# 02_-_MCU.net
KiCad netlist of a schematic drawn in Altium Designer
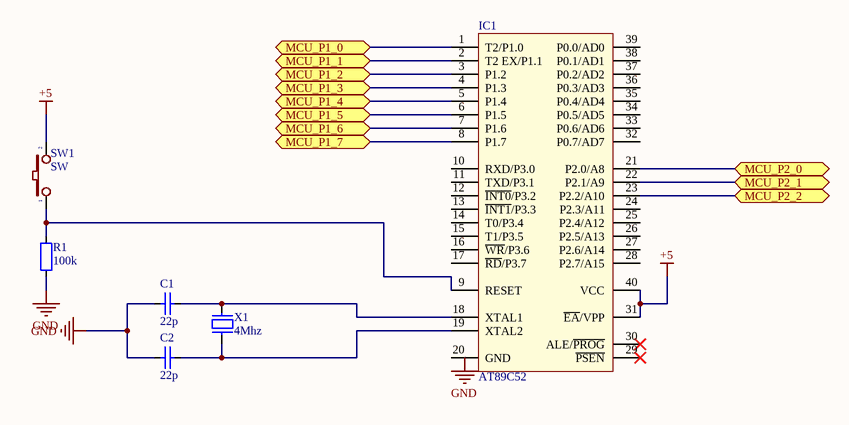
[diagram p0: 02 - MCU.SchDoc]

(export (version "E")
  (design (tool "Eeschema 10.0.6"))
  (components
    (comp (ref "C1")
      (value "22p")
      (footprint "CAP_0402")
      (description "Capacitor")
      (fields (field (name "PUBLISHER") "Altium Limited"))
      (libsource (lib "My Library.~(5)") (part "CapSMD"))
    )
    (comp (ref "C2")
      (value "22p")
      (footprint "CAP_0402")
      (description "Capacitor")
      (fields (field (name "PUBLISHER") "Altium Limited"))
      (libsource (lib "My Library.~(5)") (part "CapSMD"))
    )
    (comp (ref "IC1")
      (value "AT89C52")
      (footprint "DIP40/W0.6")
      (description "Atmel AT89C52, 8k Byte Flash Memory , 40 Pin")
      (libsource (lib "My Library.~(1)") (part "AT89C52"))
    )
    (comp (ref "R1")
      (value "100k")
      (footprint "RES-SMD-0101")
      (description "Resistor")
      (fields
        (field (name "MANUFACTURER") "Generic Components")
        (field (name "PUBLISHER") "Altium Hobart Technology Centre")
      )
      (libsource (lib "My Library.~(5)") (part "Resistor - SMD"))
    )
    (comp (ref "SW1")
      (value "SW")
      (footprint "SW2")
      (description "Switch button 2 pin")
      (libsource (lib "My Library.~(5)") (part "SW2"))
    )
    (comp (ref "X1")
      (value "4Mhz")
      (footprint "XT2")
      (description "Crystal For all Crystal 2pin.")
      (libsource (lib "My Library.~(1)") (part "XT2"))
    )
  )
  (nets
    (net (code "1") (name "+5") (class "Default")
      (node (ref "IC1") (pin "31") (pinfunction "~{EA}/VPP_31") (pintype "passive"))
      (node (ref "IC1") (pin "40") (pinfunction "VCC_40") (pintype "power_in"))
      (node (ref "SW1") (pin "2") (pinfunction "2_2") (pintype "passive"))
    )
    (net (code "2") (name "/MCU_P1_0") (class "Default")
      (node (ref "IC1") (pin "1") (pinfunction "T2/P1.0_1") (pintype "passive"))
    )
    (net (code "3") (name "/MCU_P1_1") (class "Default")
      (node (ref "IC1") (pin "2") (pinfunction "T2_EX/P1.1_2") (pintype "passive"))
    )
    (net (code "4") (name "/MCU_P1_2") (class "Default")
      (node (ref "IC1") (pin "3") (pinfunction "P1.2_3") (pintype "passive"))
    )
    (net (code "5") (name "/MCU_P1_3") (class "Default")
      (node (ref "IC1") (pin "4") (pinfunction "P1.3_4") (pintype "passive"))
    )
    (net (code "6") (name "/MCU_P1_4") (class "Default")
      (node (ref "IC1") (pin "5") (pinfunction "P1.4_5") (pintype "passive"))
    )
    (net (code "7") (name "/MCU_P1_5") (class "Default")
      (node (ref "IC1") (pin "6") (pinfunction "P1.5_6") (pintype "passive"))
    )
    (net (code "8") (name "/MCU_P1_6") (class "Default")
      (node (ref "IC1") (pin "7") (pinfunction "P1.6_7") (pintype "passive"))
    )
    (net (code "9") (name "/MCU_P1_7") (class "Default")
      (node (ref "IC1") (pin "8") (pinfunction "P1.7_8") (pintype "passive"))
    )
    (net (code "10") (name "/MCU_P2_0") (class "Default")
      (node (ref "IC1") (pin "21") (pinfunction "P2.0/A8_21") (pintype "passive"))
    )
    (net (code "11") (name "/MCU_P2_1") (class "Default")
      (node (ref "IC1") (pin "22") (pinfunction "P2.1/A9_22") (pintype "passive"))
    )
    (net (code "12") (name "/MCU_P2_2") (class "Default")
      (node (ref "IC1") (pin "23") (pinfunction "P2.2/A10_23") (pintype "passive"))
    )
    (net (code "13") (name "GND") (class "Default")
      (node (ref "C1") (pin "1") (pinfunction "1_1") (pintype "passive"))
      (node (ref "C2") (pin "1") (pinfunction "1_1") (pintype "passive"))
      (node (ref "R1") (pin "1") (pinfunction "1_1") (pintype "passive"))
    )
    (net (code "14") (name "Net-(IC1-RESET)") (class "Default")
      (node (ref "IC1") (pin "9") (pinfunction "RESET_9") (pintype "passive"))
      (node (ref "R1") (pin "2") (pinfunction "2_2") (pintype "passive"))
      (node (ref "SW1") (pin "1") (pinfunction "1_1") (pintype "passive"))
    )
    (net (code "15") (name "Net-(IC1-XTAL1)") (class "Default")
      (node (ref "C1") (pin "2") (pinfunction "2_2") (pintype "passive"))
      (node (ref "IC1") (pin "18") (pinfunction "XTAL1_18") (pintype "passive"))
      (node (ref "X1") (pin "2") (pinfunction "2_2") (pintype "passive"))
    )
    (net (code "16") (name "Net-(IC1-XTAL2)") (class "Default")
      (node (ref "C2") (pin "2") (pinfunction "2_2") (pintype "passive"))
      (node (ref "IC1") (pin "19") (pinfunction "XTAL2_19") (pintype "passive"))
      (node (ref "X1") (pin "1") (pinfunction "1_1") (pintype "passive"))
    )
    (net (code "17") (name "unconnected-(IC1-ALE{slash}~{PROG}-Pad30)") (class "Default")
      (node (ref "IC1") (pin "30") (pinfunction "ALE/~{PROG}_30") (pintype "passive+no_connect"))
    )
    (net (code "18") (name "unconnected-(IC1-GND-Pad20)") (class "Default")
      (node (ref "IC1") (pin "20") (pinfunction "GND_20") (pintype "open_emitter"))
    )
    (net (code "19") (name "unconnected-(IC1-P0.0{slash}AD0-Pad39)") (class "Default")
      (node (ref "IC1") (pin "39") (pinfunction "P0.0/AD0_39") (pintype "passive"))
    )
    (net (code "20") (name "unconnected-(IC1-P0.1{slash}AD1-Pad38)") (class "Default")
      (node (ref "IC1") (pin "38") (pinfunction "P0.1/AD1_38") (pintype "passive"))
    )
    (net (code "21") (name "unconnected-(IC1-P0.2{slash}AD2-Pad37)") (class "Default")
      (node (ref "IC1") (pin "37") (pinfunction "P0.2/AD2_37") (pintype "passive"))
    )
    (net (code "22") (name "unconnected-(IC1-P0.3{slash}AD3-Pad36)") (class "Default")
      (node (ref "IC1") (pin "36") (pinfunction "P0.3/AD3_36") (pintype "passive"))
    )
    (net (code "23") (name "unconnected-(IC1-P0.4{slash}AD4-Pad35)") (class "Default")
      (node (ref "IC1") (pin "35") (pinfunction "P0.4/AD4_35") (pintype "passive"))
    )
    (net (code "24") (name "unconnected-(IC1-P0.5{slash}AD5-Pad34)") (class "Default")
      (node (ref "IC1") (pin "34") (pinfunction "P0.5/AD5_34") (pintype "passive"))
    )
    (net (code "25") (name "unconnected-(IC1-P0.6{slash}AD6-Pad33)") (class "Default")
      (node (ref "IC1") (pin "33") (pinfunction "P0.6/AD6_33") (pintype "passive"))
    )
    (net (code "26") (name "unconnected-(IC1-P0.7{slash}AD7-Pad32)") (class "Default")
      (node (ref "IC1") (pin "32") (pinfunction "P0.7/AD7_32") (pintype "passive"))
    )
    (net (code "27") (name "unconnected-(IC1-P2.3{slash}A11-Pad24)") (class "Default")
      (node (ref "IC1") (pin "24") (pinfunction "P2.3/A11_24") (pintype "passive"))
    )
    (net (code "28") (name "unconnected-(IC1-P2.4{slash}A12-Pad25)") (class "Default")
      (node (ref "IC1") (pin "25") (pinfunction "P2.4/A12_25") (pintype "passive"))
    )
    (net (code "29") (name "unconnected-(IC1-P2.5{slash}A13-Pad26)") (class "Default")
      (node (ref "IC1") (pin "26") (pinfunction "P2.5/A13_26") (pintype "passive"))
    )
    (net (code "30") (name "unconnected-(IC1-P2.6{slash}A14-Pad27)") (class "Default")
      (node (ref "IC1") (pin "27") (pinfunction "P2.6/A14_27") (pintype "passive"))
    )
    (net (code "31") (name "unconnected-(IC1-P2.7{slash}A15-Pad28)") (class "Default")
      (node (ref "IC1") (pin "28") (pinfunction "P2.7/A15_28") (pintype "passive"))
    )
    (net (code "32") (name "unconnected-(IC1-RXD{slash}P3.0-Pad10)") (class "Default")
      (node (ref "IC1") (pin "10") (pinfunction "RXD/P3.0_10") (pintype "passive"))
    )
    (net (code "33") (name "unconnected-(IC1-T0{slash}P3.4-Pad14)") (class "Default")
      (node (ref "IC1") (pin "14") (pinfunction "T0/P3.4_14") (pintype "passive"))
    )
    (net (code "34") (name "unconnected-(IC1-T1{slash}P3.5-Pad15)") (class "Default")
      (node (ref "IC1") (pin "15") (pinfunction "T1/P3.5_15") (pintype "passive"))
    )
    (net (code "35") (name "unconnected-(IC1-TXD{slash}P3.1-Pad11)") (class "Default")
      (node (ref "IC1") (pin "11") (pinfunction "TXD/P3.1_11") (pintype "passive"))
    )
    (net (code "36") (name "unconnected-(IC1-~{INT0}{slash}P3.2-Pad12)") (class "Default")
      (node (ref "IC1") (pin "12") (pinfunction "~{INT0}/P3.2_12") (pintype "passive"))
    )
    (net (code "37") (name "unconnected-(IC1-~{INT1}{slash}P3.3-Pad13)") (class "Default")
      (node (ref "IC1") (pin "13") (pinfunction "~{INT1}/P3.3_13") (pintype "passive"))
    )
    (net (code "38") (name "unconnected-(IC1-~{PSEN}-Pad29)") (class "Default")
      (node (ref "IC1") (pin "29") (pinfunction "~{PSEN}_29") (pintype "passive+no_connect"))
    )
    (net (code "39") (name "unconnected-(IC1-~{RD}{slash}P3.7-Pad17)") (class "Default")
      (node (ref "IC1") (pin "17") (pinfunction "~{RD}/P3.7_17") (pintype "passive"))
    )
    (net (code "40") (name "unconnected-(IC1-~{WR}{slash}P3.6-Pad16)") (class "Default")
      (node (ref "IC1") (pin "16") (pinfunction "~{WR}/P3.6_16") (pintype "passive"))
    )
  )
)
